# Crowtail-I2C_Hub_v0_9.net
KiCad netlist of a schematic drawn in EAGLE
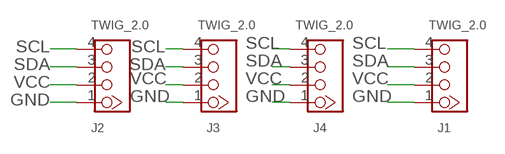
[diagram p0: schematic, sheet 1]

(export (version "E")
  (design (tool "Eeschema 10.0.6"))
  (components
    (comp (ref "J1")
      (value "TWIG_2.0")
      (footprint "eagle-import:2.0_1X4")
      (libsource (lib "eagle-import") (part "TWIG_2.0"))
    )
    (comp (ref "J2")
      (value "TWIG_2.0")
      (footprint "eagle-import:2.0_1X4")
      (libsource (lib "eagle-import") (part "TWIG_2.0"))
    )
    (comp (ref "J3")
      (value "TWIG_2.0")
      (footprint "eagle-import:2.0_1X4")
      (libsource (lib "eagle-import") (part "TWIG_2.0"))
    )
    (comp (ref "J4")
      (value "TWIG_2.0")
      (footprint "eagle-import:2.0_1X4")
      (libsource (lib "eagle-import") (part "TWIG_2.0"))
    )
  )
  (nets
    (net (code "1") (name "/GND") (class "Default")
      (node (ref "J1") (pin "1") (pinfunction "1_1") (pintype "bidirectional"))
      (node (ref "J2") (pin "1") (pinfunction "1_1") (pintype "bidirectional"))
      (node (ref "J3") (pin "1") (pinfunction "1_1") (pintype "bidirectional"))
      (node (ref "J4") (pin "1") (pinfunction "1_1") (pintype "bidirectional"))
    )
    (net (code "2") (name "/SCL") (class "Default")
      (node (ref "J1") (pin "4") (pinfunction "4_4") (pintype "bidirectional"))
      (node (ref "J2") (pin "4") (pinfunction "4_4") (pintype "bidirectional"))
      (node (ref "J3") (pin "4") (pinfunction "4_4") (pintype "bidirectional"))
      (node (ref "J4") (pin "4") (pinfunction "4_4") (pintype "bidirectional"))
    )
    (net (code "3") (name "/SDA") (class "Default")
      (node (ref "J1") (pin "3") (pinfunction "3_3") (pintype "bidirectional"))
      (node (ref "J2") (pin "3") (pinfunction "3_3") (pintype "bidirectional"))
      (node (ref "J3") (pin "3") (pinfunction "3_3") (pintype "bidirectional"))
      (node (ref "J4") (pin "3") (pinfunction "3_3") (pintype "bidirectional"))
    )
    (net (code "4") (name "/VCC") (class "Default")
      (node (ref "J1") (pin "2") (pinfunction "2_2") (pintype "bidirectional"))
      (node (ref "J2") (pin "2") (pinfunction "2_2") (pintype "bidirectional"))
      (node (ref "J3") (pin "2") (pinfunction "2_2") (pintype "bidirectional"))
      (node (ref "J4") (pin "2") (pinfunction "2_2") (pintype "bidirectional"))
    )
  )
)
